# OpenPLCv0_2_0_USBPortTypeB.net
KiCad netlist of a schematic drawn in Altium Designer
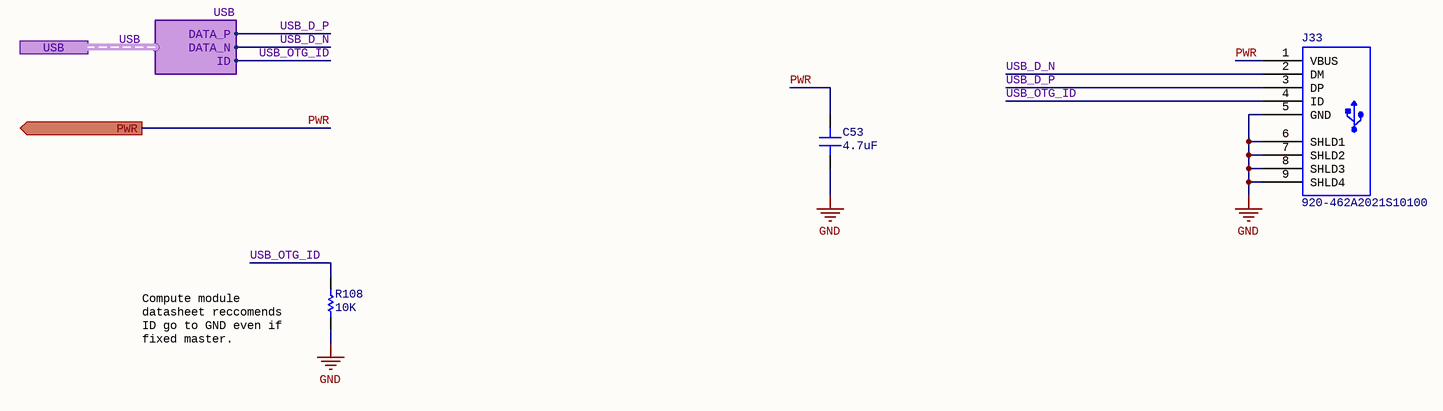
[diagram p0: OpenPLCv0.2.0_USBPortTypeB.SchDoc]

(export (version "E")
  (design (tool "Eeschema 10.0.6"))
  (components
    (comp (ref "C53")
      (value "CC0603KRX5R6BB475")
      (footprint "SMD_CAP_0603(0201)_N")
      (description "4.7uF ±10% 10V X5R 0603 Multilayer Ceramic Capacitors MLCC - SMD/SMT RoHS")
      (fields (field (name "TOLERANCE") "10%") (field (name "CAPACITANCE") "4.7uF"))
      (libsource (lib "BrauV2_Capacitor") (part "4.7uF 0603 10V 10%"))
    )
    (comp (ref "J33")
      (value "920-462A2021S10100")
      (footprint "920-462A2021S10100")
      (description "USB - Mini B Female USB 2 5 SMD USB Connectors RoHS")
      (libsource (lib "BrauV2_Connector") (part "920-462A2021S10100"))
    )
    (comp (ref "R108")
      (value "RC0402FR-0710KL")
      (footprint "SMD_RES_0402(1005)_N")
      (description "10kΩ ±1% 1/16W ±100ppm/℃ 0402 Chip Resistor - Surface Mount RoHS")
      (fields (field (name "TOLERANCE") "1%") (field (name "RESISTANCE") "10K"))
      (libsource (lib "BrauV2_Resistor") (part "10K 0402 1% 1/16W"))
    )
  )
  (nets
    (net (code "2") (name "/PWR") (class "Default")
      (node (ref "C53") (pin "2") (pinfunction "2_2") (pintype "passive"))
      (node (ref "J33") (pin "1") (pinfunction "VBUS_1") (pintype "passive"))
    )
    (net (code "3") (name "/USB_D_N") (class "Default")
      (node (ref "J33") (pin "2") (pinfunction "DM_2") (pintype "passive"))
    )
    (net (code "4") (name "/USB_D_P") (class "Default")
      (node (ref "J33") (pin "3") (pinfunction "DP_3") (pintype "passive"))
    )
    (net (code "5") (name "/USB_OTG_ID") (class "Default")
      (node (ref "J33") (pin "4") (pinfunction "ID_4") (pintype "passive"))
      (node (ref "R108") (pin "2") (pinfunction "2_2") (pintype "passive"))
    )
    (net (code "7") (name "GND") (class "Default")
      (node (ref "C53") (pin "1") (pinfunction "1_1") (pintype "passive"))
      (node (ref "J33") (pin "5") (pinfunction "GND_5") (pintype "passive"))
      (node (ref "J33") (pin "6") (pinfunction "SHLD1_6") (pintype "passive"))
      (node (ref "J33") (pin "7") (pinfunction "SHLD2_7") (pintype "passive"))
      (node (ref "J33") (pin "8") (pinfunction "SHLD3_8") (pintype "passive"))
      (node (ref "J33") (pin "9") (pinfunction "SHLD4_9") (pintype "passive"))
      (node (ref "R108") (pin "1") (pinfunction "1_1") (pintype "passive"))
    )
  )
)
